# Sheet6.net
KiCad netlist of a schematic drawn in Altium Designer
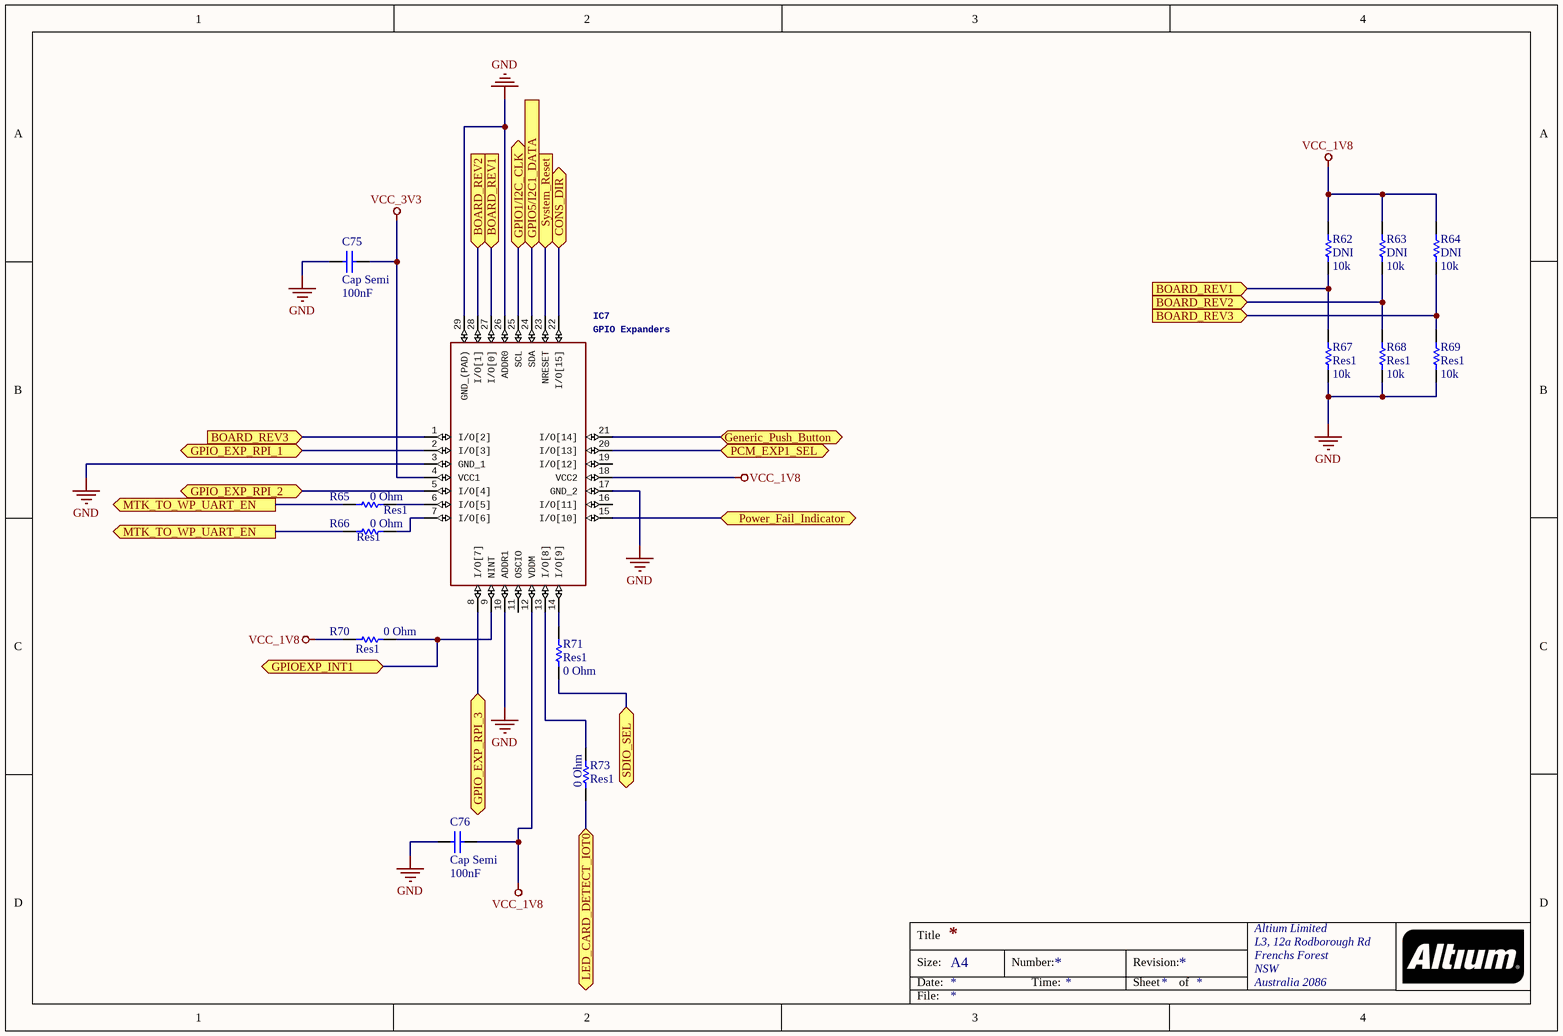
[diagram p0: Sheet6.SchDoc]

(export (version "E")
  (design (tool "Eeschema 10.0.6"))
  (components
    (comp (ref "C75")
      (value "Cap Semi")
      (footprint "CAP 0402/1005")
      (description "Capacitor (Semiconductor SIM Model)")
      (fields (field (name "PART NUMBER") "LMK105BJ104KV-F") (field (name "ALTIUM_VALUE") "100nF"))
      (libsource (lib "Miscellaneous Devices") (part "Cap Semi"))
    )
    (comp (ref "C76")
      (value "Cap Semi")
      (footprint "CAP 0402/1005")
      (description "Capacitor (Semiconductor SIM Model)")
      (fields (field (name "PART NUMBER") "LMK105BJ104KV-F") (field (name "ALTIUM_VALUE") "100nF"))
      (libsource (lib "Miscellaneous Devices") (part "Cap Semi"))
    )
    (comp (ref "IC7")
      (value "GPIO Expanders")
      (footprint "QFN40P400X400X60-29N")
      (fields
        (field (name "MANUFACTURER_PART_NUMBER") "SX1509BIULTRT")
        (field (name "MOUSER_PART_NUMBER") "947-SX1509BIULTRT")
      )
      (libsource (lib "SX1509BIULTRT") (part "SX1509BIULTRT"))
    )
    (comp (ref "R62")
      (value "DNI")
      (footprint "RES 0402/1005")
      (description "Resistor")
      (fields (field (name "PART NUMBER") "MCR01MZPF1002") (field (name "ALTIUM_VALUE") "10k"))
      (libsource (lib "Miscellaneous Devices") (part "Res1"))
    )
    (comp (ref "R63")
      (value "DNI")
      (footprint "RES 0402/1005")
      (description "Resistor")
      (fields (field (name "PART NUMBER") "MCR01MZPF1002") (field (name "ALTIUM_VALUE") "10k"))
      (libsource (lib "Miscellaneous Devices") (part "Res1"))
    )
    (comp (ref "R64")
      (value "DNI")
      (footprint "RES 0402/1005")
      (description "Resistor")
      (fields (field (name "PART NUMBER") "MCR01MZPF1002") (field (name "ALTIUM_VALUE") "10k"))
      (libsource (lib "Miscellaneous Devices") (part "Res1"))
    )
    (comp (ref "R65")
      (value "Res1")
      (footprint "RES 0402/1005")
      (description "Resistor")
      (fields (field (name "PART NUMBER") "RK73Z1ETTP") (field (name "ALTIUM_VALUE") "0 Ohm"))
      (libsource (lib "Miscellaneous Devices") (part "Res1"))
    )
    (comp (ref "R66")
      (value "Res1")
      (footprint "RES 0402/1005")
      (description "Resistor")
      (fields (field (name "PART NUMBER") "RK73Z1ETTP") (field (name "ALTIUM_VALUE") "0 Ohm"))
      (libsource (lib "Miscellaneous Devices") (part "Res1"))
    )
    (comp (ref "R67")
      (value "Res1")
      (footprint "RES 0402/1005")
      (description "Resistor")
      (fields (field (name "PART NUMBER") "MCR01MZPF1002") (field (name "ALTIUM_VALUE") "10k"))
      (libsource (lib "Miscellaneous Devices") (part "Res1"))
    )
    (comp (ref "R68")
      (value "Res1")
      (footprint "RES 0402/1005")
      (description "Resistor")
      (fields (field (name "PART NUMBER") "MCR01MZPF1002") (field (name "ALTIUM_VALUE") "10k"))
      (libsource (lib "Miscellaneous Devices") (part "Res1"))
    )
    (comp (ref "R69")
      (value "Res1")
      (footprint "RES 0402/1005")
      (description "Resistor")
      (fields (field (name "PART NUMBER") "MCR01MZPF1002") (field (name "ALTIUM_VALUE") "10k"))
      (libsource (lib "Miscellaneous Devices") (part "Res1"))
    )
    (comp (ref "R70")
      (value "Res1")
      (footprint "RES 0402/1005")
      (description "Resistor")
      (fields (field (name "PART NUMBER") "RK73Z1ETTP") (field (name "ALTIUM_VALUE") "0 Ohm"))
      (libsource (lib "Miscellaneous Devices") (part "Res1"))
    )
    (comp (ref "R71")
      (value "Res1")
      (footprint "RES 0402/1005")
      (description "Resistor")
      (fields (field (name "PART NUMBER") "RK73Z1ETTP") (field (name "ALTIUM_VALUE") "0 Ohm"))
      (libsource (lib "Miscellaneous Devices") (part "Res1"))
    )
    (comp (ref "R73")
      (value "Res1")
      (footprint "RES 0402/1005")
      (description "Resistor")
      (fields (field (name "PART NUMBER") "RK73Z1ETTP") (field (name "ALTIUM_VALUE") "0 Ohm"))
      (libsource (lib "Miscellaneous Devices") (part "Res1"))
    )
  )
  (nets
    (net (code "1") (name "/BOARD_REV1") (class "Default")
      (node (ref "IC7") (pin "27") (pinfunction "I/O[0]_27") (pintype "bidirectional"))
      (node (ref "R62") (pin "2") (pinfunction "2_2") (pintype "passive"))
      (node (ref "R67") (pin "1") (pinfunction "1_1") (pintype "passive"))
    )
    (net (code "2") (name "/BOARD_REV2") (class "Default")
      (node (ref "IC7") (pin "28") (pinfunction "I/O[1]_28") (pintype "bidirectional"))
      (node (ref "R63") (pin "2") (pinfunction "2_2") (pintype "passive"))
      (node (ref "R68") (pin "1") (pinfunction "1_1") (pintype "passive"))
    )
    (net (code "3") (name "/BOARD_REV3") (class "Default")
      (node (ref "IC7") (pin "1") (pinfunction "I/O[2]_1") (pintype "bidirectional"))
      (node (ref "R64") (pin "2") (pinfunction "2_2") (pintype "passive"))
      (node (ref "R69") (pin "1") (pinfunction "1_1") (pintype "passive"))
    )
    (net (code "4") (name "/CONS_DIR") (class "Default")
      (node (ref "IC7") (pin "22") (pinfunction "I/O[15]_22") (pintype "bidirectional"))
    )
    (net (code "5") (name "/GPIO1{slash}I2C_CLK") (class "Default")
      (node (ref "IC7") (pin "25") (pinfunction "SCL_25") (pintype "bidirectional"))
    )
    (net (code "6") (name "/GPIO5{slash}I2C1_DATA") (class "Default")
      (node (ref "IC7") (pin "24") (pinfunction "SDA_24") (pintype "bidirectional"))
    )
    (net (code "7") (name "/GPIOEXP_INT1") (class "Default")
      (node (ref "IC7") (pin "9") (pinfunction "NINT_9") (pintype "bidirectional"))
      (node (ref "R70") (pin "2") (pinfunction "2_2") (pintype "passive"))
    )
    (net (code "8") (name "/GPIO_EXP_RPI_1") (class "Default")
      (node (ref "IC7") (pin "2") (pinfunction "I/O[3]_2") (pintype "bidirectional"))
    )
    (net (code "9") (name "/GPIO_EXP_RPI_2") (class "Default")
      (node (ref "IC7") (pin "5") (pinfunction "I/O[4]_5") (pintype "bidirectional"))
    )
    (net (code "10") (name "/GPIO_EXP_RPI_3") (class "Default")
      (node (ref "IC7") (pin "8") (pinfunction "I/O[7]_8") (pintype "bidirectional"))
    )
    (net (code "11") (name "/Generic_Push_Button") (class "Default")
      (node (ref "IC7") (pin "21") (pinfunction "I/O[14]_21") (pintype "bidirectional"))
    )
    (net (code "12") (name "/LED_CARD_DETECT_IOT0") (class "Default")
      (node (ref "R73") (pin "2") (pinfunction "2_2") (pintype "passive"))
    )
    (net (code "13") (name "/MTK_TO_WP_UART_EN") (class "Default")
      (node (ref "R65") (pin "2") (pinfunction "2_2") (pintype "passive"))
      (node (ref "R66") (pin "2") (pinfunction "2_2") (pintype "passive"))
    )
    (net (code "14") (name "/PCM_EXP1_SEL") (class "Default")
      (node (ref "IC7") (pin "20") (pinfunction "I/O[13]_20") (pintype "bidirectional"))
    )
    (net (code "15") (name "/Power_Fail_Indicator") (class "Default")
      (node (ref "IC7") (pin "15") (pinfunction "I/O[10]_15") (pintype "bidirectional"))
    )
    (net (code "16") (name "/SDIO_SEL") (class "Default")
      (node (ref "R71") (pin "2") (pinfunction "2_2") (pintype "passive"))
    )
    (net (code "17") (name "/System_Reset") (class "Default")
      (node (ref "IC7") (pin "23") (pinfunction "NRESET_23") (pintype "bidirectional"))
    )
    (net (code "18") (name "GND") (class "Default")
      (node (ref "C75") (pin "2") (pinfunction "2_2") (pintype "passive"))
      (node (ref "C76") (pin "2") (pinfunction "2_2") (pintype "passive"))
      (node (ref "IC7") (pin "10") (pinfunction "ADDR1_10") (pintype "bidirectional"))
      (node (ref "IC7") (pin "17") (pinfunction "GND_2_17") (pintype "bidirectional"))
      (node (ref "IC7") (pin "26") (pinfunction "ADDR0_26") (pintype "bidirectional"))
      (node (ref "IC7") (pin "29") (pinfunction "GND_(PAD)_29") (pintype "bidirectional"))
      (node (ref "IC7") (pin "3") (pinfunction "GND_1_3") (pintype "bidirectional"))
      (node (ref "R67") (pin "2") (pinfunction "2_2") (pintype "passive"))
      (node (ref "R68") (pin "2") (pinfunction "2_2") (pintype "passive"))
      (node (ref "R69") (pin "2") (pinfunction "2_2") (pintype "passive"))
    )
    (net (code "19") (name "Net-(IC7-I{slash}O[5])") (class "Default")
      (node (ref "IC7") (pin "6") (pinfunction "I/O[5]_6") (pintype "bidirectional"))
      (node (ref "R65") (pin "1") (pinfunction "1_1") (pintype "passive"))
    )
    (net (code "20") (name "Net-(IC7-I{slash}O[6])") (class "Default")
      (node (ref "IC7") (pin "7") (pinfunction "I/O[6]_7") (pintype "bidirectional"))
      (node (ref "R66") (pin "1") (pinfunction "1_1") (pintype "passive"))
    )
    (net (code "21") (name "Net-(IC7-I{slash}O[8])") (class "Default")
      (node (ref "IC7") (pin "13") (pinfunction "I/O[8]_13") (pintype "bidirectional"))
      (node (ref "R73") (pin "1") (pinfunction "1_1") (pintype "passive"))
    )
    (net (code "22") (name "Net-(IC7-I{slash}O[9])") (class "Default")
      (node (ref "IC7") (pin "14") (pinfunction "I/O[9]_14") (pintype "bidirectional"))
      (node (ref "R71") (pin "1") (pinfunction "1_1") (pintype "passive"))
    )
    (net (code "23") (name "VCC_1V8") (class "Default")
      (node (ref "C76") (pin "1") (pinfunction "1_1") (pintype "passive"))
      (node (ref "IC7") (pin "12") (pinfunction "VDDM_12") (pintype "bidirectional"))
      (node (ref "IC7") (pin "18") (pinfunction "VCC2_18") (pintype "bidirectional"))
      (node (ref "R62") (pin "1") (pinfunction "1_1") (pintype "passive"))
      (node (ref "R63") (pin "1") (pinfunction "1_1") (pintype "passive"))
      (node (ref "R64") (pin "1") (pinfunction "1_1") (pintype "passive"))
      (node (ref "R70") (pin "1") (pinfunction "1_1") (pintype "passive"))
    )
    (net (code "24") (name "VCC_3V3") (class "Default")
      (node (ref "C75") (pin "1") (pinfunction "1_1") (pintype "passive"))
      (node (ref "IC7") (pin "4") (pinfunction "VCC1_4") (pintype "bidirectional"))
    )
    (net (code "25") (name "unconnected-(IC7-I{slash}O[11]-Pad16)") (class "Default")
      (node (ref "IC7") (pin "16") (pinfunction "I/O[11]_16") (pintype "bidirectional"))
    )
    (net (code "26") (name "unconnected-(IC7-I{slash}O[12]-Pad19)") (class "Default")
      (node (ref "IC7") (pin "19") (pinfunction "I/O[12]_19") (pintype "bidirectional"))
    )
    (net (code "27") (name "unconnected-(IC7-OSCIO-Pad11)") (class "Default")
      (node (ref "IC7") (pin "11") (pinfunction "OSCIO_11") (pintype "bidirectional"))
    )
  )
)
